# DIY.net
KiCad netlist of a schematic drawn in EAGLE
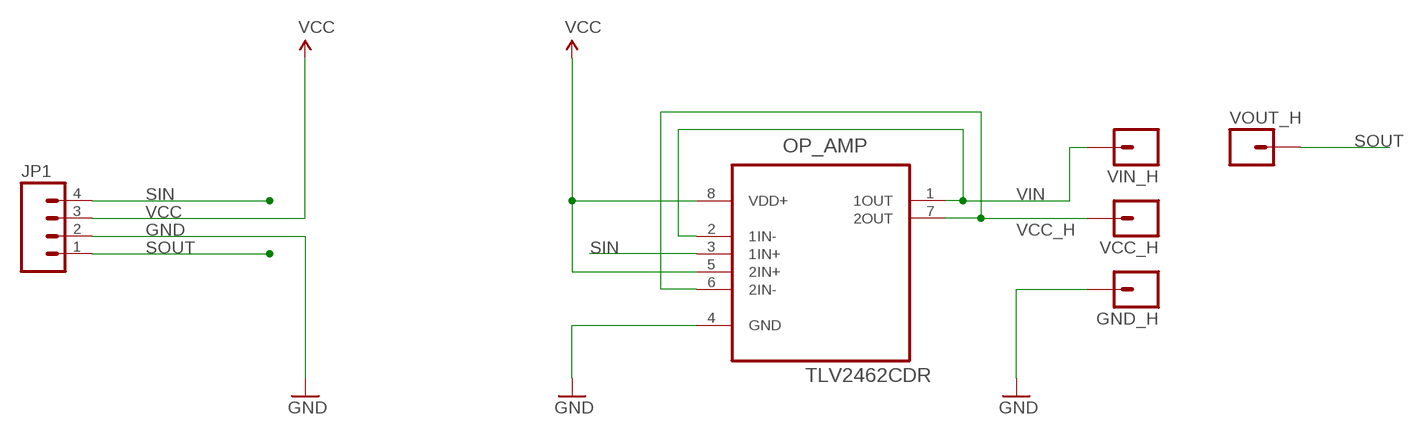
[diagram p0: schematic, sheet 1]

(export (version "E")
  (design (tool "Eeschema 10.0.6"))
  (components
    (comp (ref "GND_H")
      (value "M01PTH")
      (footprint "eagle-import:1X01")
      (libsource (lib "eagle-import") (part "M01PTH"))
    )
    (comp (ref "JP1")
      (value "M04PTH")
      (footprint "eagle-import:1X04")
      (libsource (lib "eagle-import") (part "M04PTH"))
    )
    (comp (ref "OP_AMP")
      (value "TLV2462CDR")
      (footprint "eagle-import:SOIC127P600X175-8N")
      (libsource (lib "eagle-import") (part "TLV2462CDR"))
    )
    (comp (ref "VCC_H")
      (value "M01PTH")
      (footprint "eagle-import:1X01")
      (libsource (lib "eagle-import") (part "M01PTH"))
    )
    (comp (ref "VIN_H")
      (value "M01PTH")
      (footprint "eagle-import:1X01")
      (libsource (lib "eagle-import") (part "M01PTH"))
    )
    (comp (ref "VOUT_H")
      (value "M01PTH")
      (footprint "eagle-import:1X01")
      (libsource (lib "eagle-import") (part "M01PTH"))
    )
  )
  (nets
    (net (code "1") (name "/SIN") (class "Default")
      (node (ref "JP1") (pin "4") (pinfunction "4_4") (pintype "passive"))
      (node (ref "OP_AMP") (pin "3") (pinfunction "1IN+_3") (pintype "input"))
    )
    (net (code "2") (name "/SOUT") (class "Default")
      (node (ref "JP1") (pin "1") (pinfunction "1_1") (pintype "passive"))
      (node (ref "VOUT_H") (pin "1") (pinfunction "1_1") (pintype "passive"))
    )
    (net (code "3") (name "/VCC_H") (class "Default")
      (node (ref "OP_AMP") (pin "6") (pinfunction "2IN-_6") (pintype "input"))
      (node (ref "OP_AMP") (pin "7") (pinfunction "2OUT_7") (pintype "output"))
      (node (ref "VCC_H") (pin "1") (pinfunction "1_1") (pintype "passive"))
    )
    (net (code "4") (name "/VIN") (class "Default")
      (node (ref "OP_AMP") (pin "1") (pinfunction "1OUT_1") (pintype "output"))
      (node (ref "OP_AMP") (pin "2") (pinfunction "1IN-_2") (pintype "input"))
      (node (ref "VIN_H") (pin "1") (pinfunction "1_1") (pintype "passive"))
    )
    (net (code "5") (name "GND") (class "Default")
      (node (ref "GND_H") (pin "1") (pinfunction "1_1") (pintype "passive"))
      (node (ref "JP1") (pin "2") (pinfunction "2_2") (pintype "passive"))
      (node (ref "OP_AMP") (pin "4") (pinfunction "GND_4") (pintype "passive"))
    )
    (net (code "6") (name "VCC") (class "Default")
      (node (ref "JP1") (pin "3") (pinfunction "3_3") (pintype "passive"))
      (node (ref "OP_AMP") (pin "5") (pinfunction "2IN+_5") (pintype "input"))
      (node (ref "OP_AMP") (pin "8") (pinfunction "VDD+_8") (pintype "power_in"))
    )
  )
)
